# SCH_LM2596-5V-Buck-Converter-SMD_2024-10.net
KiCad netlist of a schematic drawn in EasyEDA
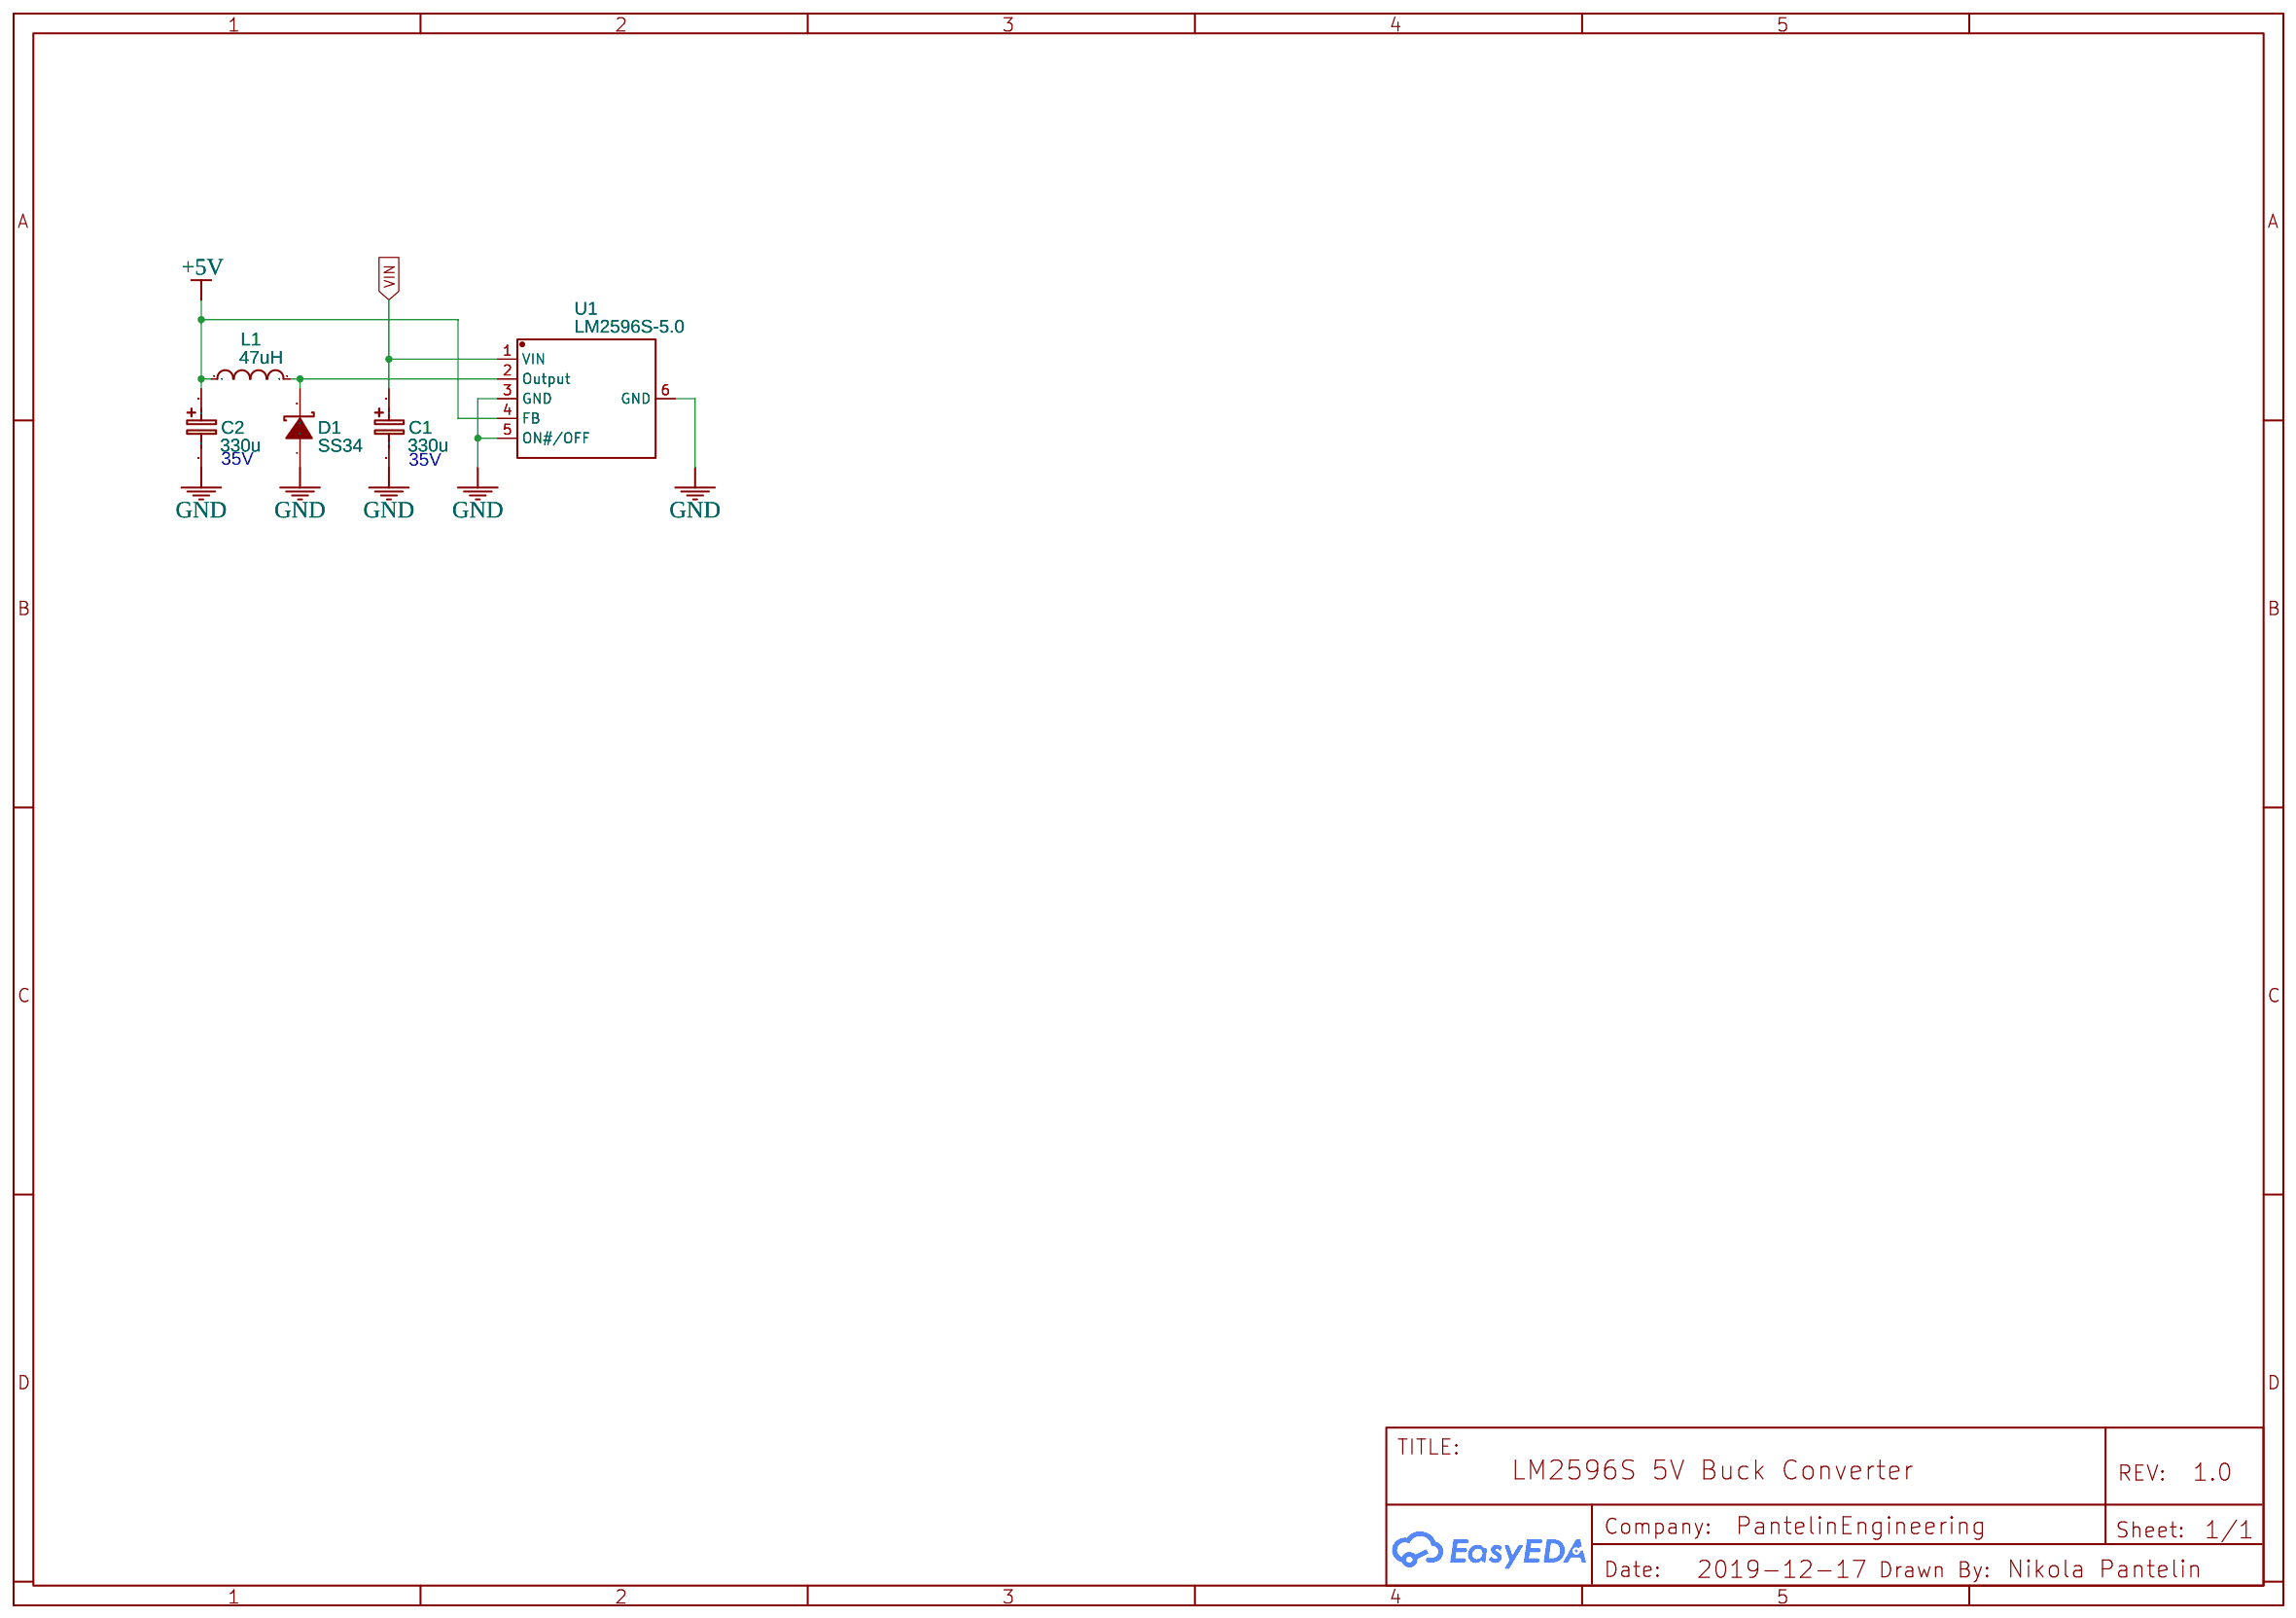
[diagram p0: schematic sheet]

(export (version "E")
  (design (tool "Eeschema 10.0.6"))
  (components
    (comp (ref "C1")
      (value "330u")
      (fields (field (name "Manufacturer Part") "?"))
      (libsource (lib "") (part "Cap_Electrolytic(SMD)_D8.0XH10.5_EU"))
    )
    (comp (ref "C2")
      (value "330u")
      (fields (field (name "Manufacturer Part") "?"))
      (libsource (lib "") (part "Cap_Electrolytic(SMD)_D8.0XH10.5_EU_1"))
    )
    (comp (ref "D1")
      (value "SS34")
      (fields (field (name "Manufacturer") "Yenji"))
      (libsource (lib "") (part "Unknown_145_210"))
    )
    (comp (ref "L1")
      (value "47uH")
      (fields (field (name "Manufacturer Part") "CDRH127NP-470MC") (field (name "Manufacturer") "Sumida"))
      (libsource (lib "") (part "CDRH127NP-470MC"))
    )
    (comp (ref "U1")
      (value "LM2596S-5.0")
      (fields
        (field (name "Manufacturer Part") "LM2596S-5.0/NOPB")
        (field (name "Manufacturer") "Texas Instruments")
      )
      (libsource (lib "") (part "Unknown_290_195"))
    )
  )
  (nets
    (net (code "1") (name "+5V") (class "Default")
      (node (ref "C2") (pin "1") (pinfunction "1_1") (pintype "unspecified"))
      (node (ref "L1") (pin "1") (pinfunction "1_1") (pintype "unspecified"))
      (node (ref "U1") (pin "4") (pinfunction "FB_4") (pintype "unspecified"))
    )
    (net (code "2") (name "GND") (class "Default")
      (node (ref "C1") (pin "2") (pinfunction "2_2") (pintype "unspecified"))
      (node (ref "C2") (pin "2") (pinfunction "2_2") (pintype "unspecified"))
      (node (ref "D1") (pin "1") (pinfunction "A_1") (pintype "unspecified"))
      (node (ref "U1") (pin "3") (pinfunction "GND_3") (pintype "unspecified"))
      (node (ref "U1") (pin "5") (pinfunction "ON#/OFF_5") (pintype "unspecified"))
      (node (ref "U1") (pin "6") (pinfunction "GND_6") (pintype "unspecified"))
    )
    (net (code "3") (name "Net-(D1-K)") (class "Default")
      (node (ref "D1") (pin "2") (pinfunction "K_2") (pintype "unspecified"))
      (node (ref "L1") (pin "2") (pinfunction "2_2") (pintype "unspecified"))
      (node (ref "U1") (pin "2") (pinfunction "Output_2") (pintype "unspecified"))
    )
    (net (code "4") (name "VIN") (class "Default")
      (node (ref "C1") (pin "1") (pinfunction "1_1") (pintype "unspecified"))
      (node (ref "U1") (pin "1") (pinfunction "VIN_1") (pintype "unspecified"))
    )
  )
)
